# PCEngine_RGB_Adapter.net
KiCad netlist of a schematic drawn in EAGLE
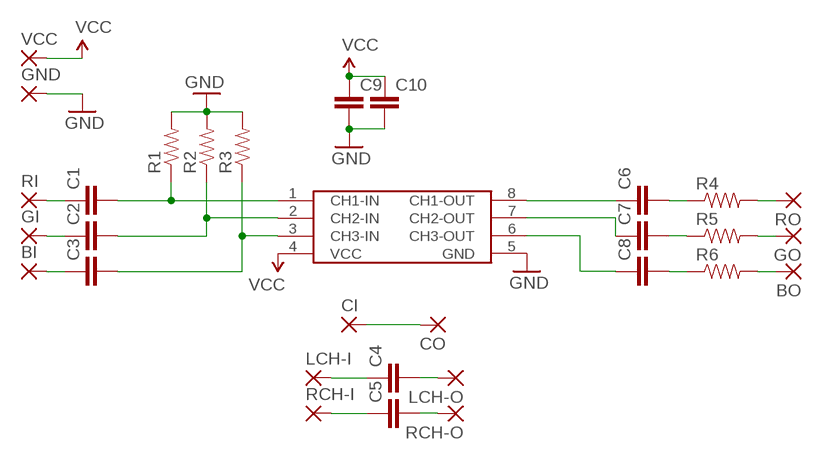
[diagram p0: schematic, sheet 1]

(export (version "E")
  (design (tool "Eeschema 10.0.6"))
  (components
    (comp (ref "BI")
      (value "WIREPADSMD1,27-254")
      (footprint "eagle-import:SMD1,27-2,54")
      (libsource (lib "eagle-import") (part "WIREPADSMD1,27-254"))
    )
    (comp (ref "BO")
      (value "WIREPADSMD1,27-254")
      (footprint "eagle-import:SMD1,27-2,54")
      (libsource (lib "eagle-import") (part "WIREPADSMD1,27-254"))
    )
    (comp (ref "C1")
      (value "CAP0805")
      (footprint "eagle-import:0805")
      (libsource (lib "eagle-import") (part "CAP0805"))
    )
    (comp (ref "C2")
      (value "CAP0805")
      (footprint "eagle-import:0805")
      (libsource (lib "eagle-import") (part "CAP0805"))
    )
    (comp (ref "C3")
      (value "CAP0805")
      (footprint "eagle-import:0805")
      (libsource (lib "eagle-import") (part "CAP0805"))
    )
    (comp (ref "C4")
      (value "CAP0805")
      (footprint "eagle-import:0805")
      (libsource (lib "eagle-import") (part "CAP0805"))
    )
    (comp (ref "C5")
      (value "CAP0805")
      (footprint "eagle-import:0805")
      (libsource (lib "eagle-import") (part "CAP0805"))
    )
    (comp (ref "C6")
      (value "CAP1210")
      (footprint "eagle-import:1210")
      (libsource (lib "eagle-import") (part "CAP1210"))
    )
    (comp (ref "C7")
      (value "CAP1210")
      (footprint "eagle-import:1210")
      (libsource (lib "eagle-import") (part "CAP1210"))
    )
    (comp (ref "C8")
      (value "CAP1210")
      (footprint "eagle-import:1210")
      (libsource (lib "eagle-import") (part "CAP1210"))
    )
    (comp (ref "C9")
      (value "CAP0805")
      (footprint "eagle-import:0805")
      (libsource (lib "eagle-import") (part "CAP0805"))
    )
    (comp (ref "C10")
      (value "CAP0805")
      (footprint "eagle-import:0805")
      (libsource (lib "eagle-import") (part "CAP0805"))
    )
    (comp (ref "CI")
      (value "WIREPADSMD1,27-254")
      (footprint "eagle-import:SMD1,27-2,54")
      (libsource (lib "eagle-import") (part "WIREPADSMD1,27-254"))
    )
    (comp (ref "CO")
      (value "WIREPADSMD1,27-254")
      (footprint "eagle-import:SMD1,27-2,54")
      (libsource (lib "eagle-import") (part "WIREPADSMD1,27-254"))
    )
    (comp (ref "GI")
      (value "WIREPADSMD1,27-254")
      (footprint "eagle-import:SMD1,27-2,54")
      (libsource (lib "eagle-import") (part "WIREPADSMD1,27-254"))
    )
    (comp (ref "GND")
      (value "WIREPADSMD1,27-254")
      (footprint "eagle-import:SMD1,27-2,54")
      (libsource (lib "eagle-import") (part "WIREPADSMD1,27-254"))
    )
    (comp (ref "GO")
      (value "WIREPADSMD1,27-254")
      (footprint "eagle-import:SMD1,27-2,54")
      (libsource (lib "eagle-import") (part "WIREPADSMD1,27-254"))
    )
    (comp (ref "LCH-I")
      (value "WIREPADSMD1,27-254")
      (footprint "eagle-import:SMD1,27-2,54")
      (libsource (lib "eagle-import") (part "WIREPADSMD1,27-254"))
    )
    (comp (ref "LCH-O")
      (value "WIREPADSMD1,27-254")
      (footprint "eagle-import:SMD1,27-2,54")
      (libsource (lib "eagle-import") (part "WIREPADSMD1,27-254"))
    )
    (comp (ref "R1")
      (value "RESISTOR0805-RES")
      (footprint "eagle-import:0805")
      (libsource (lib "eagle-import") (part "RESISTOR0805-RES"))
    )
    (comp (ref "R2")
      (value "RESISTOR0805-RES")
      (footprint "eagle-import:0805")
      (libsource (lib "eagle-import") (part "RESISTOR0805-RES"))
    )
    (comp (ref "R3")
      (value "RESISTOR0805-RES")
      (footprint "eagle-import:0805")
      (libsource (lib "eagle-import") (part "RESISTOR0805-RES"))
    )
    (comp (ref "R4")
      (value "RESISTOR0805-RES")
      (footprint "eagle-import:0805")
      (libsource (lib "eagle-import") (part "RESISTOR0805-RES"))
    )
    (comp (ref "R5")
      (value "RESISTOR0805-RES")
      (footprint "eagle-import:0805")
      (libsource (lib "eagle-import") (part "RESISTOR0805-RES"))
    )
    (comp (ref "R6")
      (value "RESISTOR0805-RES")
      (footprint "eagle-import:0805")
      (libsource (lib "eagle-import") (part "RESISTOR0805-RES"))
    )
    (comp (ref "RCH-I")
      (value "WIREPADSMD1,27-254")
      (footprint "eagle-import:SMD1,27-2,54")
      (libsource (lib "eagle-import") (part "WIREPADSMD1,27-254"))
    )
    (comp (ref "RCH-O")
      (value "WIREPADSMD1,27-254")
      (footprint "eagle-import:SMD1,27-2,54")
      (libsource (lib "eagle-import") (part "WIREPADSMD1,27-254"))
    )
    (comp (ref "RI")
      (value "WIREPADSMD1,27-254")
      (footprint "eagle-import:SMD1,27-2,54")
      (libsource (lib "eagle-import") (part "WIREPADSMD1,27-254"))
    )
    (comp (ref "RO")
      (value "WIREPADSMD1,27-254")
      (footprint "eagle-import:SMD1,27-2,54")
      (libsource (lib "eagle-import") (part "WIREPADSMD1,27-254"))
    )
    (comp (ref "U$1")
      (value "THS7314SMD")
      (footprint "eagle-import:SOIC8")
      (libsource (lib "eagle-import") (part "THS7314SMD"))
    )
    (comp (ref "VCC")
      (value "WIREPADSMD1,27-254")
      (footprint "eagle-import:SMD1,27-2,54")
      (libsource (lib "eagle-import") (part "WIREPADSMD1,27-254"))
    )
  )
  (nets
    (net (code "1") (name "GND") (class "Default")
      (node (ref "C10") (pin "2") (pinfunction "2_2") (pintype "passive"))
      (node (ref "C9") (pin "2") (pinfunction "2_2") (pintype "passive"))
      (node (ref "GND") (pin "1") (pinfunction "P_1") (pintype "passive"))
      (node (ref "R1") (pin "2") (pinfunction "2_2") (pintype "passive"))
      (node (ref "R2") (pin "2") (pinfunction "2_2") (pintype "passive"))
      (node (ref "R3") (pin "2") (pinfunction "2_2") (pintype "passive"))
      (node (ref "U$1") (pin "5") (pinfunction "GND_5") (pintype "power_in"))
    )
    (net (code "2") (name "Net-(BI-P)") (class "Default")
      (node (ref "BI") (pin "1") (pinfunction "P_1") (pintype "passive"))
      (node (ref "C3") (pin "1") (pinfunction "1_1") (pintype "passive"))
    )
    (net (code "3") (name "Net-(BO-P)") (class "Default")
      (node (ref "BO") (pin "1") (pinfunction "P_1") (pintype "passive"))
      (node (ref "R6") (pin "2") (pinfunction "2_2") (pintype "passive"))
    )
    (net (code "4") (name "Net-(C6-Pad2)") (class "Default")
      (node (ref "C6") (pin "2") (pinfunction "2_2") (pintype "passive"))
      (node (ref "R4") (pin "1") (pinfunction "1_1") (pintype "passive"))
    )
    (net (code "5") (name "Net-(C7-Pad2)") (class "Default")
      (node (ref "C7") (pin "2") (pinfunction "2_2") (pintype "passive"))
      (node (ref "R5") (pin "1") (pinfunction "1_1") (pintype "passive"))
    )
    (net (code "6") (name "Net-(C8-Pad2)") (class "Default")
      (node (ref "C8") (pin "2") (pinfunction "2_2") (pintype "passive"))
      (node (ref "R6") (pin "1") (pinfunction "1_1") (pintype "passive"))
    )
    (net (code "7") (name "Net-(CI-P)") (class "Default")
      (node (ref "CI") (pin "1") (pinfunction "P_1") (pintype "passive"))
      (node (ref "CO") (pin "1") (pinfunction "P_1") (pintype "passive"))
    )
    (net (code "8") (name "Net-(GI-P)") (class "Default")
      (node (ref "C2") (pin "1") (pinfunction "1_1") (pintype "passive"))
      (node (ref "GI") (pin "1") (pinfunction "P_1") (pintype "passive"))
    )
    (net (code "9") (name "Net-(GO-P)") (class "Default")
      (node (ref "GO") (pin "1") (pinfunction "P_1") (pintype "passive"))
      (node (ref "R5") (pin "2") (pinfunction "2_2") (pintype "passive"))
    )
    (net (code "10") (name "Net-(LCH-I-P)") (class "Default")
      (node (ref "C4") (pin "1") (pinfunction "1_1") (pintype "passive"))
      (node (ref "LCH-I") (pin "1") (pinfunction "P_1") (pintype "passive"))
    )
    (net (code "11") (name "Net-(LCH-O-P)") (class "Default")
      (node (ref "C4") (pin "2") (pinfunction "2_2") (pintype "passive"))
      (node (ref "LCH-O") (pin "1") (pinfunction "P_1") (pintype "passive"))
    )
    (net (code "12") (name "Net-(RCH-I-P)") (class "Default")
      (node (ref "C5") (pin "1") (pinfunction "1_1") (pintype "passive"))
      (node (ref "RCH-I") (pin "1") (pinfunction "P_1") (pintype "passive"))
    )
    (net (code "13") (name "Net-(RCH-O-P)") (class "Default")
      (node (ref "C5") (pin "2") (pinfunction "2_2") (pintype "passive"))
      (node (ref "RCH-O") (pin "1") (pinfunction "P_1") (pintype "passive"))
    )
    (net (code "14") (name "Net-(RI-P)") (class "Default")
      (node (ref "C1") (pin "1") (pinfunction "1_1") (pintype "passive"))
      (node (ref "RI") (pin "1") (pinfunction "P_1") (pintype "passive"))
    )
    (net (code "15") (name "Net-(RO-P)") (class "Default")
      (node (ref "R4") (pin "2") (pinfunction "2_2") (pintype "passive"))
      (node (ref "RO") (pin "1") (pinfunction "P_1") (pintype "passive"))
    )
    (net (code "16") (name "Net-(U$1-CH1-IN)") (class "Default")
      (node (ref "C1") (pin "2") (pinfunction "2_2") (pintype "passive"))
      (node (ref "R1") (pin "1") (pinfunction "1_1") (pintype "passive"))
      (node (ref "U$1") (pin "1") (pinfunction "CH1-IN_1") (pintype "input"))
    )
    (net (code "17") (name "Net-(U$1-CH1-OUT)") (class "Default")
      (node (ref "C6") (pin "1") (pinfunction "1_1") (pintype "passive"))
      (node (ref "U$1") (pin "8") (pinfunction "CH1-OUT_8") (pintype "output"))
    )
    (net (code "18") (name "Net-(U$1-CH2-IN)") (class "Default")
      (node (ref "C2") (pin "2") (pinfunction "2_2") (pintype "passive"))
      (node (ref "R2") (pin "1") (pinfunction "1_1") (pintype "passive"))
      (node (ref "U$1") (pin "2") (pinfunction "CH2-IN_2") (pintype "input"))
    )
    (net (code "19") (name "Net-(U$1-CH2-OUT)") (class "Default")
      (node (ref "C7") (pin "1") (pinfunction "1_1") (pintype "passive"))
      (node (ref "U$1") (pin "7") (pinfunction "CH2-OUT_7") (pintype "output"))
    )
    (net (code "20") (name "Net-(U$1-CH3-IN)") (class "Default")
      (node (ref "C3") (pin "2") (pinfunction "2_2") (pintype "passive"))
      (node (ref "R3") (pin "1") (pinfunction "1_1") (pintype "passive"))
      (node (ref "U$1") (pin "3") (pinfunction "CH3-IN_3") (pintype "input"))
    )
    (net (code "21") (name "Net-(U$1-CH3-OUT)") (class "Default")
      (node (ref "C8") (pin "1") (pinfunction "1_1") (pintype "passive"))
      (node (ref "U$1") (pin "6") (pinfunction "CH3-OUT_6") (pintype "output"))
    )
    (net (code "22") (name "VCC") (class "Default")
      (node (ref "C10") (pin "1") (pinfunction "1_1") (pintype "passive"))
      (node (ref "C9") (pin "1") (pinfunction "1_1") (pintype "passive"))
      (node (ref "U$1") (pin "4") (pinfunction "VCC_4") (pintype "power_in"))
      (node (ref "VCC") (pin "1") (pinfunction "P_1") (pintype "passive"))
    )
  )
)
